# UART-LA.net
KiCad netlist of a schematic drawn in Altium Designer
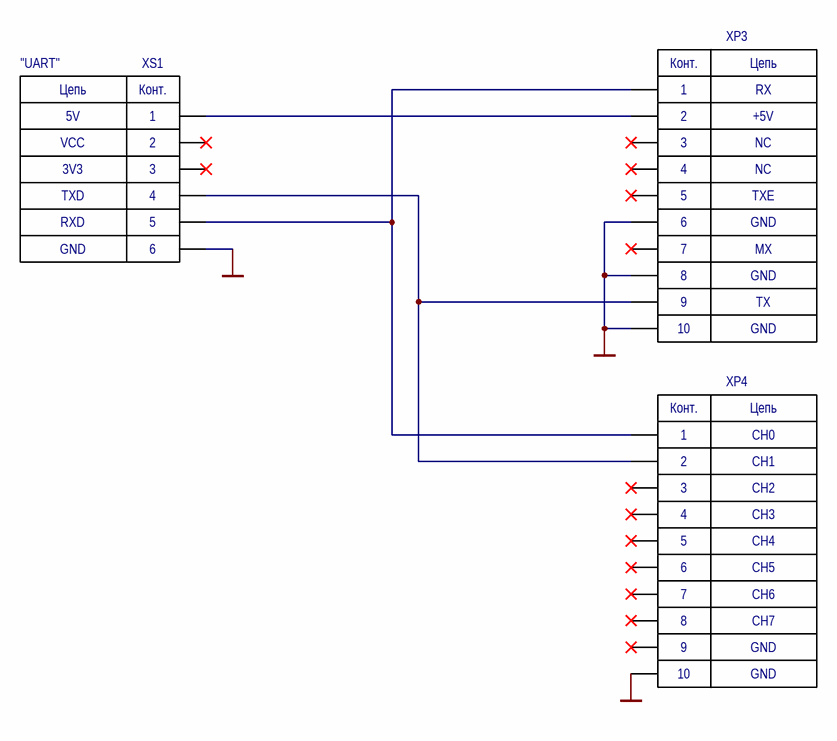
[diagram p0: UART-LA.SchDoc]

(export (version "E")
  (design (tool "Eeschema 10.0.6"))
  (components
    (comp (ref "XP3")
      (value "IDC-10MS")
      (footprint "IDC-10MS")
      (description "Box Header Pitch 2.54mm")
      (fields
        (field (name "CIRCUIT7") "MX")
        (field (name "CIRCUIT8") "GND")
        (field (name "CIRCUIT9") "TX")
        (field (name "CIRCUIT10") "GND")
        (field (name "CIRCUIT6") "GND")
        (field (name "CIRCUIT4") "NC")
        (field (name "CIRCUIT5") "TXE")
        (field (name "CIRCUIT3") "NC")
        (field (name "CIRCUIT2") "+5V")
        (field (name "CIRCUIT1") "RX")
      )
      (libsource (lib "Connectors") (part "IDC-10MS"))
    )
    (comp (ref "XP4")
      (value "IDC-10MS")
      (footprint "IDC-10MS")
      (description "Box Header Pitch 2.54mm")
      (fields
        (field (name "CIRCUIT7") "CH6")
        (field (name "CIRCUIT8") "CH7")
        (field (name "CIRCUIT9") "GND")
        (field (name "CIRCUIT10") "GND")
        (field (name "CIRCUIT6") "CH5")
        (field (name "CIRCUIT4") "CH3")
        (field (name "CIRCUIT5") "CH4")
        (field (name "CIRCUIT3") "CH2")
        (field (name "CIRCUIT2") "CH1")
        (field (name "CIRCUIT1") "CH0")
      )
      (libsource (lib "Connectors") (part "IDC-10MS"))
    )
    (comp (ref "XS1")
      (value "PBS-6R")
      (footprint "PBS-6R-left")
      (description "Female Header R/A type Pitch 2.54mm")
      (fields
        (field (name "CIRCUIT4") "TXD")
        (field (name "CIRCUIT5") "RXD")
        (field (name "CIRCUIT6") "GND")
        (field (name "CIRCUIT3") "3V3")
        (field (name "CIRCUIT1") "5V")
        (field (name "CIRCUIT2") "VCC")
        (field (name "LABEL") "\"UART\"")
      )
      (libsource (lib "Connectors") (part "PBS-6R"))
    )
  )
  (nets
    (net (code "1") (name "GND") (class "Default")
      (node (ref "XP3") (pin "10") (pinfunction "10_10") (pintype "passive"))
      (node (ref "XP3") (pin "6") (pinfunction "6_6") (pintype "passive"))
      (node (ref "XP3") (pin "8") (pinfunction "8_8") (pintype "passive"))
      (node (ref "XP4") (pin "10") (pinfunction "10_10") (pintype "passive"))
      (node (ref "XS1") (pin "6") (pinfunction "6_6") (pintype "passive"))
    )
    (net (code "2") (name "Net-(XP3-Pad1)") (class "Default")
      (node (ref "XP3") (pin "1") (pinfunction "1_1") (pintype "passive"))
      (node (ref "XP4") (pin "1") (pinfunction "1_1") (pintype "passive"))
      (node (ref "XS1") (pin "5") (pinfunction "5_5") (pintype "passive"))
    )
    (net (code "3") (name "Net-(XP3-Pad2)") (class "Default")
      (node (ref "XP3") (pin "2") (pinfunction "2_2") (pintype "passive"))
      (node (ref "XS1") (pin "1") (pinfunction "1_1") (pintype "passive"))
    )
    (net (code "4") (name "Net-(XP3-Pad9)") (class "Default")
      (node (ref "XP3") (pin "9") (pinfunction "9_9") (pintype "passive"))
      (node (ref "XP4") (pin "2") (pinfunction "2_2") (pintype "passive"))
      (node (ref "XS1") (pin "4") (pinfunction "4_4") (pintype "passive"))
    )
    (net (code "5") (name "unconnected-(XP3-Pad3)") (class "Default")
      (node (ref "XP3") (pin "3") (pinfunction "3_3") (pintype "passive+no_connect"))
    )
    (net (code "6") (name "unconnected-(XP3-Pad4)") (class "Default")
      (node (ref "XP3") (pin "4") (pinfunction "4_4") (pintype "passive+no_connect"))
    )
    (net (code "7") (name "unconnected-(XP3-Pad5)") (class "Default")
      (node (ref "XP3") (pin "5") (pinfunction "5_5") (pintype "passive+no_connect"))
    )
    (net (code "8") (name "unconnected-(XP3-Pad7)") (class "Default")
      (node (ref "XP3") (pin "7") (pinfunction "7_7") (pintype "passive+no_connect"))
    )
    (net (code "9") (name "unconnected-(XP4-Pad3)") (class "Default")
      (node (ref "XP4") (pin "3") (pinfunction "3_3") (pintype "passive+no_connect"))
    )
    (net (code "10") (name "unconnected-(XP4-Pad4)") (class "Default")
      (node (ref "XP4") (pin "4") (pinfunction "4_4") (pintype "passive+no_connect"))
    )
    (net (code "11") (name "unconnected-(XP4-Pad5)") (class "Default")
      (node (ref "XP4") (pin "5") (pinfunction "5_5") (pintype "passive+no_connect"))
    )
    (net (code "12") (name "unconnected-(XP4-Pad6)") (class "Default")
      (node (ref "XP4") (pin "6") (pinfunction "6_6") (pintype "passive+no_connect"))
    )
    (net (code "13") (name "unconnected-(XP4-Pad7)") (class "Default")
      (node (ref "XP4") (pin "7") (pinfunction "7_7") (pintype "passive+no_connect"))
    )
    (net (code "14") (name "unconnected-(XP4-Pad8)") (class "Default")
      (node (ref "XP4") (pin "8") (pinfunction "8_8") (pintype "passive+no_connect"))
    )
    (net (code "15") (name "unconnected-(XP4-Pad9)") (class "Default")
      (node (ref "XP4") (pin "9") (pinfunction "9_9") (pintype "passive+no_connect"))
    )
    (net (code "16") (name "unconnected-(XS1-Pad2)") (class "Default")
      (node (ref "XS1") (pin "2") (pinfunction "2_2") (pintype "passive+no_connect"))
    )
    (net (code "17") (name "unconnected-(XS1-Pad3)") (class "Default")
      (node (ref "XS1") (pin "3") (pinfunction "3_3") (pintype "passive+no_connect"))
    )
  )
)
